# S7CAS-PLEIADES-CARTE-MERE_Pxx_MECANICAL.net
KiCad netlist of a schematic drawn in Altium Designer
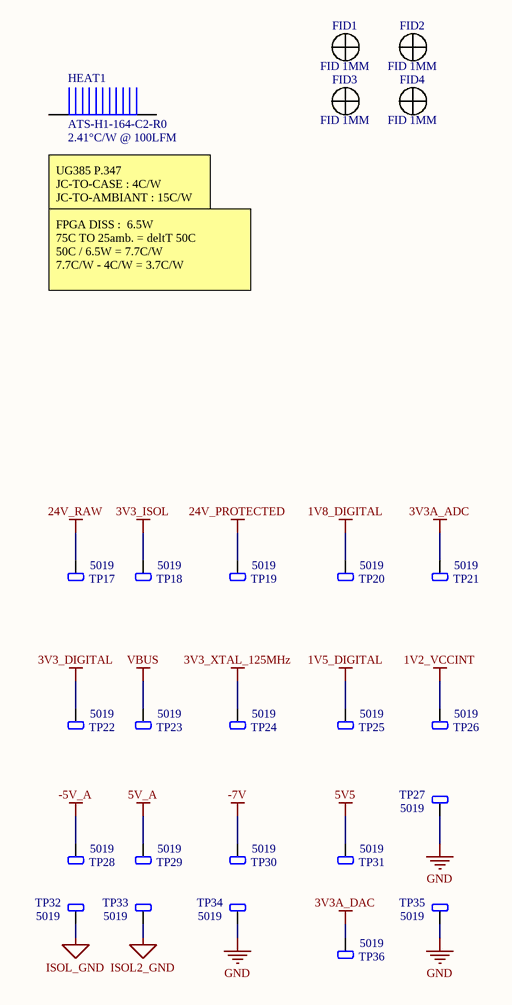
[diagram p0: S7CAS-PLEIADES-CARTE-MERE_Pxx_MECANICAL.SchDoc]

(export (version "E")
  (design (tool "Eeschema 10.0.6"))
  (components
    (comp (ref "FID1")
      (value "FID 1MM")
      (footprint "FID_CIRCLE_1MM - PASTE_MASK")
      (description "FID - FIDUCIAL 1MM CIRCLE DOUBLE-SIDED - 1MM")
      (fields
        (field (name "CREATEDBY/DATE") "Jonathan Bouchard 2018-07-23")
        (field (name "VERIFIEDBY") "Caroline Paulin - 25 juillet 2018")
      )
      (libsource (lib "S7CAS_LIB2023") (part "FID_CIRCLE_1MM_PASTE_MASK"))
    )
    (comp (ref "FID2")
      (value "FID 1MM")
      (footprint "FID_CIRCLE_1MM - PASTE_MASK")
      (description "FID - FIDUCIAL 1MM CIRCLE DOUBLE-SIDED - 1MM")
      (fields
        (field (name "CREATEDBY/DATE") "Jonathan Bouchard 2018-07-23")
        (field (name "VERIFIEDBY") "Caroline Paulin - 25 juillet 2018")
      )
      (libsource (lib "S7CAS_LIB2023") (part "FID_CIRCLE_1MM_PASTE_MASK"))
    )
    (comp (ref "FID3")
      (value "FID 1MM")
      (footprint "FID_CIRCLE_1MM - PASTE_MASK")
      (description "FID - FIDUCIAL 1MM CIRCLE DOUBLE-SIDED - 1MM")
      (fields
        (field (name "CREATEDBY/DATE") "Jonathan Bouchard 2018-07-23")
        (field (name "VERIFIEDBY") "Caroline Paulin - 25 juillet 2018")
      )
      (libsource (lib "S7CAS_LIB2023") (part "FID_CIRCLE_1MM_PASTE_MASK"))
    )
    (comp (ref "FID4")
      (value "FID 1MM")
      (footprint "FID_CIRCLE_1MM - PASTE_MASK")
      (description "FID - FIDUCIAL 1MM CIRCLE DOUBLE-SIDED - 1MM")
      (fields
        (field (name "CREATEDBY/DATE") "Jonathan Bouchard 2018-07-23")
        (field (name "VERIFIEDBY") "Caroline Paulin - 25 juillet 2018")
      )
      (libsource (lib "S7CAS_LIB2023") (part "FID_CIRCLE_1MM_PASTE_MASK"))
    )
    (comp (ref "HEAT1")
      (value "ATS-H1-164-C2-R0")
      (footprint "ATS-H1-164-C2-R0")
      (description "Heatsink Aluminium")
      (fields
        (field (name "MFR") "Advanced Thermal Solutions Inc.")
        (field (name "THERMAL RESISTANCE") "2.41°C/W @ 100LFM")
      )
      (libsource (lib "S7CAS_LIB2023") (part "HEATSINK_ATS-H1-164-C2-R0"))
    )
    (comp (ref "TP17")
      (value "5019")
      (footprint "TPO_SMD_5019")
      (description "TPO - PC TEST POINT MINI - SMD")
      (fields
        (field (name "CREATEDBY/DATE") "Olivier Bernard / 5/12/2017")
        (field (name "VERIFIEDBY") "Caroline Paulin / 5 juillet 2018")
      )
      (libsource (lib "S7CAS_LIB2023") (part "TPO_SMD_5019"))
    )
    (comp (ref "TP18")
      (value "5019")
      (footprint "TPO_SMD_5019")
      (description "TPO - PC TEST POINT MINI - SMD")
      (fields
        (field (name "CREATEDBY/DATE") "Olivier Bernard / 5/12/2017")
        (field (name "VERIFIEDBY") "Caroline Paulin / 5 juillet 2018")
      )
      (libsource (lib "S7CAS_LIB2023") (part "TPO_SMD_5019"))
    )
    (comp (ref "TP19")
      (value "5019")
      (footprint "TPO_SMD_5019")
      (description "TPO - PC TEST POINT MINI - SMD")
      (fields
        (field (name "CREATEDBY/DATE") "Olivier Bernard / 5/12/2017")
        (field (name "VERIFIEDBY") "Caroline Paulin / 5 juillet 2018")
      )
      (libsource (lib "S7CAS_LIB2023") (part "TPO_SMD_5019"))
    )
    (comp (ref "TP20")
      (value "5019")
      (footprint "TPO_SMD_5019")
      (description "TPO - PC TEST POINT MINI - SMD")
      (fields
        (field (name "CREATEDBY/DATE") "Olivier Bernard / 5/12/2017")
        (field (name "VERIFIEDBY") "Caroline Paulin / 5 juillet 2018")
      )
      (libsource (lib "S7CAS_LIB2023") (part "TPO_SMD_5019"))
    )
    (comp (ref "TP21")
      (value "5019")
      (footprint "TPO_SMD_5019")
      (description "TPO - PC TEST POINT MINI - SMD")
      (fields
        (field (name "CREATEDBY/DATE") "Olivier Bernard / 5/12/2017")
        (field (name "VERIFIEDBY") "Caroline Paulin / 5 juillet 2018")
      )
      (libsource (lib "S7CAS_LIB2023") (part "TPO_SMD_5019"))
    )
    (comp (ref "TP22")
      (value "5019")
      (footprint "TPO_SMD_5019")
      (description "TPO - PC TEST POINT MINI - SMD")
      (fields
        (field (name "CREATEDBY/DATE") "Olivier Bernard / 5/12/2017")
        (field (name "VERIFIEDBY") "Caroline Paulin / 5 juillet 2018")
      )
      (libsource (lib "S7CAS_LIB2023") (part "TPO_SMD_5019"))
    )
    (comp (ref "TP23")
      (value "5019")
      (footprint "TPO_SMD_5019")
      (description "TPO - PC TEST POINT MINI - SMD")
      (fields
        (field (name "CREATEDBY/DATE") "Olivier Bernard / 5/12/2017")
        (field (name "VERIFIEDBY") "Caroline Paulin / 5 juillet 2018")
      )
      (libsource (lib "S7CAS_LIB2023") (part "TPO_SMD_5019"))
    )
    (comp (ref "TP24")
      (value "5019")
      (footprint "TPO_SMD_5019")
      (description "TPO - PC TEST POINT MINI - SMD")
      (fields
        (field (name "CREATEDBY/DATE") "Olivier Bernard / 5/12/2017")
        (field (name "VERIFIEDBY") "Caroline Paulin / 5 juillet 2018")
      )
      (libsource (lib "S7CAS_LIB2023") (part "TPO_SMD_5019"))
    )
    (comp (ref "TP25")
      (value "5019")
      (footprint "TPO_SMD_5019")
      (description "TPO - PC TEST POINT MINI - SMD")
      (fields
        (field (name "CREATEDBY/DATE") "Olivier Bernard / 5/12/2017")
        (field (name "VERIFIEDBY") "Caroline Paulin / 5 juillet 2018")
      )
      (libsource (lib "S7CAS_LIB2023") (part "TPO_SMD_5019"))
    )
    (comp (ref "TP26")
      (value "5019")
      (footprint "TPO_SMD_5019")
      (description "TPO - PC TEST POINT MINI - SMD")
      (fields
        (field (name "CREATEDBY/DATE") "Olivier Bernard / 5/12/2017")
        (field (name "VERIFIEDBY") "Caroline Paulin / 5 juillet 2018")
      )
      (libsource (lib "S7CAS_LIB2023") (part "TPO_SMD_5019"))
    )
    (comp (ref "TP27")
      (value "5019")
      (footprint "TPO_SMD_5019")
      (description "TPO - PC TEST POINT MINI - SMD")
      (fields
        (field (name "CREATEDBY/DATE") "Olivier Bernard / 5/12/2017")
        (field (name "VERIFIEDBY") "Caroline Paulin / 5 juillet 2018")
      )
      (libsource (lib "S7CAS_LIB2023") (part "TPO_SMD_5019"))
    )
    (comp (ref "TP28")
      (value "5019")
      (footprint "TPO_SMD_5019")
      (description "TPO - PC TEST POINT MINI - SMD")
      (fields
        (field (name "CREATEDBY/DATE") "Olivier Bernard / 5/12/2017")
        (field (name "VERIFIEDBY") "Caroline Paulin / 5 juillet 2018")
      )
      (libsource (lib "S7CAS_LIB2023") (part "TPO_SMD_5019"))
    )
    (comp (ref "TP29")
      (value "5019")
      (footprint "TPO_SMD_5019")
      (description "TPO - PC TEST POINT MINI - SMD")
      (fields
        (field (name "CREATEDBY/DATE") "Olivier Bernard / 5/12/2017")
        (field (name "VERIFIEDBY") "Caroline Paulin / 5 juillet 2018")
      )
      (libsource (lib "S7CAS_LIB2023") (part "TPO_SMD_5019"))
    )
    (comp (ref "TP30")
      (value "5019")
      (footprint "TPO_SMD_5019")
      (description "TPO - PC TEST POINT MINI - SMD")
      (fields
        (field (name "CREATEDBY/DATE") "Olivier Bernard / 5/12/2017")
        (field (name "VERIFIEDBY") "Caroline Paulin / 5 juillet 2018")
      )
      (libsource (lib "S7CAS_LIB2023") (part "TPO_SMD_5019"))
    )
    (comp (ref "TP31")
      (value "5019")
      (footprint "TPO_SMD_5019")
      (description "TPO - PC TEST POINT MINI - SMD")
      (fields
        (field (name "CREATEDBY/DATE") "Olivier Bernard / 5/12/2017")
        (field (name "VERIFIEDBY") "Caroline Paulin / 5 juillet 2018")
      )
      (libsource (lib "S7CAS_LIB2023") (part "TPO_SMD_5019"))
    )
    (comp (ref "TP32")
      (value "5019")
      (footprint "TPO_SMD_5019")
      (description "TPO - PC TEST POINT MINI - SMD")
      (fields
        (field (name "CREATEDBY/DATE") "Olivier Bernard / 5/12/2017")
        (field (name "VERIFIEDBY") "Caroline Paulin / 5 juillet 2018")
      )
      (libsource (lib "S7CAS_LIB2023") (part "TPO_SMD_5019"))
    )
    (comp (ref "TP33")
      (value "5019")
      (footprint "TPO_SMD_5019")
      (description "TPO - PC TEST POINT MINI - SMD")
      (fields
        (field (name "CREATEDBY/DATE") "Olivier Bernard / 5/12/2017")
        (field (name "VERIFIEDBY") "Caroline Paulin / 5 juillet 2018")
      )
      (libsource (lib "S7CAS_LIB2023") (part "TPO_SMD_5019"))
    )
    (comp (ref "TP34")
      (value "5019")
      (footprint "TPO_SMD_5019")
      (description "TPO - PC TEST POINT MINI - SMD")
      (fields
        (field (name "CREATEDBY/DATE") "Olivier Bernard / 5/12/2017")
        (field (name "VERIFIEDBY") "Caroline Paulin / 5 juillet 2018")
      )
      (libsource (lib "S7CAS_LIB2023") (part "TPO_SMD_5019"))
    )
    (comp (ref "TP35")
      (value "5019")
      (footprint "TPO_SMD_5019")
      (description "TPO - PC TEST POINT MINI - SMD")
      (fields
        (field (name "CREATEDBY/DATE") "Olivier Bernard / 5/12/2017")
        (field (name "VERIFIEDBY") "Caroline Paulin / 5 juillet 2018")
      )
      (libsource (lib "S7CAS_LIB2023") (part "TPO_SMD_5019"))
    )
    (comp (ref "TP36")
      (value "5019")
      (footprint "TPO_SMD_5019")
      (description "TPO - PC TEST POINT MINI - SMD")
      (fields
        (field (name "CREATEDBY/DATE") "Olivier Bernard / 5/12/2017")
        (field (name "VERIFIEDBY") "Caroline Paulin / 5 juillet 2018")
      )
      (libsource (lib "S7CAS_LIB2023") (part "TPO_SMD_5019"))
    )
  )
  (nets
    (net (code "1") (name "-5V_A") (class "Default")
      (node (ref "TP28") (pin "1") (pinfunction "1_1") (pintype "passive"))
    )
    (net (code "2") (name "-7V") (class "Default")
      (node (ref "TP30") (pin "1") (pinfunction "1_1") (pintype "passive"))
    )
    (net (code "3") (name "1V2_VCCINT") (class "Default")
      (node (ref "TP26") (pin "1") (pinfunction "1_1") (pintype "passive"))
    )
    (net (code "4") (name "1V5_DIGITAL") (class "Default")
      (node (ref "TP25") (pin "1") (pinfunction "1_1") (pintype "passive"))
    )
    (net (code "5") (name "1V8_DIGITAL") (class "Default")
      (node (ref "TP20") (pin "1") (pinfunction "1_1") (pintype "passive"))
    )
    (net (code "6") (name "3V3A_ADC") (class "Default")
      (node (ref "TP21") (pin "1") (pinfunction "1_1") (pintype "passive"))
    )
    (net (code "7") (name "3V3A_DAC") (class "Default")
      (node (ref "TP36") (pin "1") (pinfunction "1_1") (pintype "passive"))
    )
    (net (code "8") (name "3V3_DIGITAL") (class "Default")
      (node (ref "TP22") (pin "1") (pinfunction "1_1") (pintype "passive"))
    )
    (net (code "9") (name "3V3_ISOL") (class "Default")
      (node (ref "TP18") (pin "1") (pinfunction "1_1") (pintype "passive"))
    )
    (net (code "10") (name "3V3_XTAL_125MHz") (class "Default")
      (node (ref "TP24") (pin "1") (pinfunction "1_1") (pintype "passive"))
    )
    (net (code "11") (name "5V5") (class "Default")
      (node (ref "TP31") (pin "1") (pinfunction "1_1") (pintype "passive"))
    )
    (net (code "12") (name "5V_A") (class "Default")
      (node (ref "TP29") (pin "1") (pinfunction "1_1") (pintype "passive"))
    )
    (net (code "13") (name "24V_PROTECTED") (class "Default")
      (node (ref "TP19") (pin "1") (pinfunction "1_1") (pintype "passive"))
    )
    (net (code "14") (name "24V_RAW") (class "Default")
      (node (ref "TP17") (pin "1") (pinfunction "1_1") (pintype "passive"))
    )
    (net (code "15") (name "GND") (class "Default")
      (node (ref "TP27") (pin "1") (pinfunction "1_1") (pintype "passive"))
      (node (ref "TP34") (pin "1") (pinfunction "1_1") (pintype "passive"))
      (node (ref "TP35") (pin "1") (pinfunction "1_1") (pintype "passive"))
    )
    (net (code "16") (name "ISOL2_GND") (class "Default")
      (node (ref "TP33") (pin "1") (pinfunction "1_1") (pintype "passive"))
    )
    (net (code "17") (name "ISOL_GND") (class "Default")
      (node (ref "TP32") (pin "1") (pinfunction "1_1") (pintype "passive"))
    )
    (net (code "18") (name "VBUS") (class "Default")
      (node (ref "TP23") (pin "1") (pinfunction "1_1") (pintype "passive"))
    )
    (net (code "19") (name "unconnected-(FID1-Pad1)") (class "Default")
      (node (ref "FID1") (pin "1") (pinfunction "1_1") (pintype "passive"))
    )
    (net (code "20") (name "unconnected-(FID1-Pad2)") (class "Default")
      (node (ref "FID1") (pin "2") (pinfunction "2_2") (pintype "passive"))
    )
    (net (code "21") (name "unconnected-(FID2-Pad1)") (class "Default")
      (node (ref "FID2") (pin "1") (pinfunction "1_1") (pintype "passive"))
    )
    (net (code "22") (name "unconnected-(FID2-Pad2)") (class "Default")
      (node (ref "FID2") (pin "2") (pinfunction "2_2") (pintype "passive"))
    )
    (net (code "23") (name "unconnected-(FID3-Pad1)") (class "Default")
      (node (ref "FID3") (pin "1") (pinfunction "1_1") (pintype "passive"))
    )
    (net (code "24") (name "unconnected-(FID3-Pad2)") (class "Default")
      (node (ref "FID3") (pin "2") (pinfunction "2_2") (pintype "passive"))
    )
    (net (code "25") (name "unconnected-(FID4-Pad1)") (class "Default")
      (node (ref "FID4") (pin "1") (pinfunction "1_1") (pintype "passive"))
    )
    (net (code "26") (name "unconnected-(FID4-Pad2)") (class "Default")
      (node (ref "FID4") (pin "2") (pinfunction "2_2") (pintype "passive"))
    )
    (net (code "27") (name "unconnected-(HEAT1-Pad1)") (class "Default")
      (node (ref "HEAT1") (pin "1") (pintype "passive"))
    )
    (net (code "28") (name "unconnected-(HEAT1-Pad2)") (class "Default")
      (node (ref "HEAT1") (pin "2") (pintype "passive"))
    )
  )
)
